# codec.net
KiCad netlist of a schematic drawn in Altium Designer
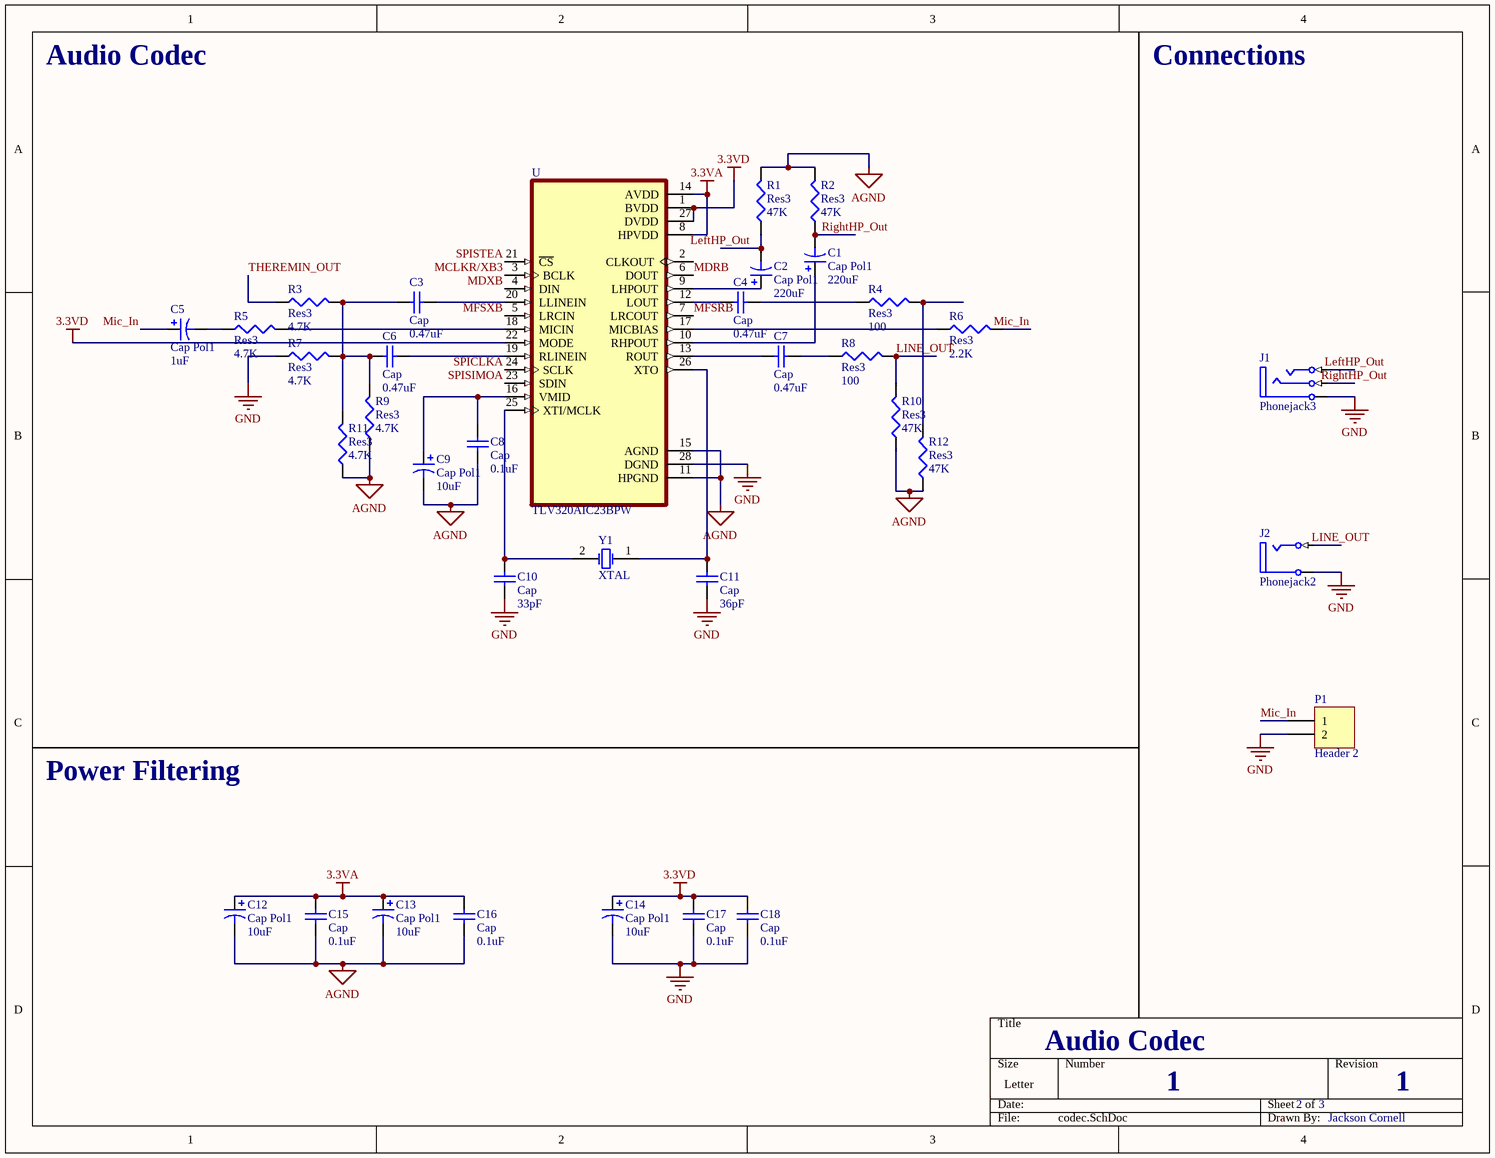
[diagram p0: codec.SchDoc]

(export (version "E")
  (design (tool "Eeschema 10.0.6"))
  (components
    (comp (ref "C1")
      (value "Cap Pol1")
      (footprint "RB7.6-15")
      (description "Polarized Capacitor (Radial)")
      (fields (field (name "ALTIUM_VALUE") "220uF") (field (name "PUBLISHER") "Altium Limited"))
      (libsource (lib "Miscellaneous Devices") (part "Cap Pol1"))
    )
    (comp (ref "C2")
      (value "Cap Pol1")
      (footprint "RB7.6-15")
      (description "Polarized Capacitor (Radial)")
      (fields (field (name "ALTIUM_VALUE") "220uF") (field (name "PUBLISHER") "Altium Limited"))
      (libsource (lib "Miscellaneous Devices") (part "Cap Pol1"))
    )
    (comp (ref "C3")
      (value "Cap")
      (footprint "RAD-0.3")
      (description "Capacitor")
      (fields (field (name "ALTIUM_VALUE") "0.47uF") (field (name "PUBLISHER") "Altium Limited"))
      (libsource (lib "Miscellaneous Devices") (part "Cap"))
    )
    (comp (ref "C4")
      (value "Cap")
      (footprint "RAD-0.3")
      (description "Capacitor")
      (fields (field (name "ALTIUM_VALUE") "0.47uF") (field (name "PUBLISHER") "Altium Limited"))
      (libsource (lib "Miscellaneous Devices") (part "Cap"))
    )
    (comp (ref "C5")
      (value "Cap Pol1")
      (footprint "RB7.6-15")
      (description "Polarized Capacitor (Radial)")
      (fields (field (name "ALTIUM_VALUE") "1uF") (field (name "PUBLISHER") "Altium Limited"))
      (libsource (lib "Miscellaneous Devices") (part "Cap Pol1"))
    )
    (comp (ref "C6")
      (value "Cap")
      (footprint "RAD-0.3")
      (description "Capacitor")
      (fields (field (name "ALTIUM_VALUE") "0.47uF") (field (name "PUBLISHER") "Altium Limited"))
      (libsource (lib "Miscellaneous Devices") (part "Cap"))
    )
    (comp (ref "C7")
      (value "Cap")
      (footprint "RAD-0.3")
      (description "Capacitor")
      (fields (field (name "ALTIUM_VALUE") "0.47uF") (field (name "PUBLISHER") "Altium Limited"))
      (libsource (lib "Miscellaneous Devices") (part "Cap"))
    )
    (comp (ref "C8")
      (value "Cap")
      (footprint "RAD-0.3")
      (description "Capacitor")
      (fields (field (name "ALTIUM_VALUE") "0.1uF") (field (name "PUBLISHER") "Altium Limited"))
      (libsource (lib "Miscellaneous Devices") (part "Cap"))
    )
    (comp (ref "C9")
      (value "Cap Pol1")
      (footprint "RB7.6-15")
      (description "Polarized Capacitor (Radial)")
      (fields (field (name "ALTIUM_VALUE") "10uF") (field (name "PUBLISHER") "Altium Limited"))
      (libsource (lib "Miscellaneous Devices") (part "Cap Pol1"))
    )
    (comp (ref "C10")
      (value "Cap")
      (footprint "RAD-0.3")
      (description "Capacitor")
      (fields (field (name "ALTIUM_VALUE") "33pF") (field (name "PUBLISHER") "Altium Limited"))
      (libsource (lib "Miscellaneous Devices") (part "Cap"))
    )
    (comp (ref "C11")
      (value "Cap")
      (footprint "RAD-0.3")
      (description "Capacitor")
      (fields (field (name "ALTIUM_VALUE") "36pF") (field (name "PUBLISHER") "Altium Limited"))
      (libsource (lib "Miscellaneous Devices") (part "Cap"))
    )
    (comp (ref "C12")
      (value "Cap Pol1")
      (footprint "RB7.6-15")
      (description "Polarized Capacitor (Radial)")
      (fields (field (name "ALTIUM_VALUE") "10uF") (field (name "PUBLISHER") "Altium Limited"))
      (libsource (lib "Miscellaneous Devices") (part "Cap Pol1"))
    )
    (comp (ref "C13")
      (value "Cap Pol1")
      (footprint "RB7.6-15")
      (description "Polarized Capacitor (Radial)")
      (fields (field (name "ALTIUM_VALUE") "10uF") (field (name "PUBLISHER") "Altium Limited"))
      (libsource (lib "Miscellaneous Devices") (part "Cap Pol1"))
    )
    (comp (ref "C14")
      (value "Cap Pol1")
      (footprint "RB7.6-15")
      (description "Polarized Capacitor (Radial)")
      (fields (field (name "ALTIUM_VALUE") "10uF") (field (name "PUBLISHER") "Altium Limited"))
      (libsource (lib "Miscellaneous Devices") (part "Cap Pol1"))
    )
    (comp (ref "C15")
      (value "Cap")
      (footprint "RAD-0.3")
      (description "Capacitor")
      (fields (field (name "ALTIUM_VALUE") "0.1uF") (field (name "PUBLISHER") "Altium Limited"))
      (libsource (lib "Miscellaneous Devices") (part "Cap"))
    )
    (comp (ref "C16")
      (value "Cap")
      (footprint "RAD-0.3")
      (description "Capacitor")
      (fields (field (name "ALTIUM_VALUE") "0.1uF") (field (name "PUBLISHER") "Altium Limited"))
      (libsource (lib "Miscellaneous Devices") (part "Cap"))
    )
    (comp (ref "C17")
      (value "Cap")
      (footprint "RAD-0.3")
      (description "Capacitor")
      (fields (field (name "ALTIUM_VALUE") "0.1uF") (field (name "PUBLISHER") "Altium Limited"))
      (libsource (lib "Miscellaneous Devices") (part "Cap"))
    )
    (comp (ref "C18")
      (value "Cap")
      (footprint "RAD-0.3")
      (description "Capacitor")
      (fields (field (name "ALTIUM_VALUE") "0.1uF") (field (name "PUBLISHER") "Altium Limited"))
      (libsource (lib "Miscellaneous Devices") (part "Cap"))
    )
    (comp (ref "J1")
      (value "Phonejack3")
      (footprint "JACK/6-V3")
      (description "Jack Socket, 1/4\" [6.5mm], Thru-Hole, Vertical, 3-Conductor Open Circuit (Non-Normalling)")
      (fields (field (name "PUBLISHER") "Altium Limited"))
      (libsource (lib "Miscellaneous Connectors") (part "Phonejack3"))
    )
    (comp (ref "J2")
      (value "Phonejack2")
      (footprint "JACK/6-V2")
      (description "Jack Socket, 1/4\" [6.5mm], Thru-Hole, Vertical, 2-Conductor Open Circuit")
      (fields (field (name "PUBLISHER") "Altium Limited"))
      (libsource (lib "Miscellaneous Connectors") (part "Phonejack2"))
    )
    (comp (ref "P1")
      (value "Header 2")
      (footprint "HDR1X2")
      (description "Header, 2-Pin")
      (fields (field (name "PUBLISHER") "Altium Limited"))
      (libsource (lib "Miscellaneous Connectors") (part "Header 2"))
    )
    (comp (ref "R1")
      (value "Res3")
      (footprint "J1-0603")
      (description "Resistor")
      (fields (field (name "ALTIUM_VALUE") "47K") (field (name "PUBLISHER") "Altium Limited"))
      (libsource (lib "Miscellaneous Devices") (part "Res3"))
    )
    (comp (ref "R2")
      (value "Res3")
      (footprint "J1-0603")
      (description "Resistor")
      (fields (field (name "ALTIUM_VALUE") "47K") (field (name "PUBLISHER") "Altium Limited"))
      (libsource (lib "Miscellaneous Devices") (part "Res3"))
    )
    (comp (ref "R3")
      (value "Res3")
      (footprint "J1-0603")
      (description "Resistor")
      (fields (field (name "ALTIUM_VALUE") "4.7K") (field (name "PUBLISHER") "Altium Limited"))
      (libsource (lib "Miscellaneous Devices") (part "Res3"))
    )
    (comp (ref "R4")
      (value "Res3")
      (footprint "J1-0603")
      (description "Resistor")
      (fields (field (name "ALTIUM_VALUE") "100") (field (name "PUBLISHER") "Altium Limited"))
      (libsource (lib "Miscellaneous Devices") (part "Res3"))
    )
    (comp (ref "R5")
      (value "Res3")
      (footprint "J1-0603")
      (description "Resistor")
      (fields (field (name "ALTIUM_VALUE") "4.7K") (field (name "PUBLISHER") "Altium Limited"))
      (libsource (lib "Miscellaneous Devices") (part "Res3"))
    )
    (comp (ref "R6")
      (value "Res3")
      (footprint "J1-0603")
      (description "Resistor")
      (fields (field (name "ALTIUM_VALUE") "2.2K") (field (name "PUBLISHER") "Altium Limited"))
      (libsource (lib "Miscellaneous Devices") (part "Res3"))
    )
    (comp (ref "R7")
      (value "Res3")
      (footprint "J1-0603")
      (description "Resistor")
      (fields (field (name "ALTIUM_VALUE") "4.7K") (field (name "PUBLISHER") "Altium Limited"))
      (libsource (lib "Miscellaneous Devices") (part "Res3"))
    )
    (comp (ref "R8")
      (value "Res3")
      (footprint "J1-0603")
      (description "Resistor")
      (fields (field (name "ALTIUM_VALUE") "100") (field (name "PUBLISHER") "Altium Limited"))
      (libsource (lib "Miscellaneous Devices") (part "Res3"))
    )
    (comp (ref "R9")
      (value "Res3")
      (footprint "J1-0603")
      (description "Resistor")
      (fields (field (name "ALTIUM_VALUE") "4.7K") (field (name "PUBLISHER") "Altium Limited"))
      (libsource (lib "Miscellaneous Devices") (part "Res3"))
    )
    (comp (ref "R10")
      (value "Res3")
      (footprint "J1-0603")
      (description "Resistor")
      (fields (field (name "ALTIUM_VALUE") "47K") (field (name "PUBLISHER") "Altium Limited"))
      (libsource (lib "Miscellaneous Devices") (part "Res3"))
    )
    (comp (ref "R11")
      (value "Res3")
      (footprint "J1-0603")
      (description "Resistor")
      (fields (field (name "ALTIUM_VALUE") "4.7K") (field (name "PUBLISHER") "Altium Limited"))
      (libsource (lib "Miscellaneous Devices") (part "Res3"))
    )
    (comp (ref "R12")
      (value "Res3")
      (footprint "J1-0603")
      (description "Resistor")
      (fields (field (name "ALTIUM_VALUE") "47K") (field (name "PUBLISHER") "Altium Limited"))
      (libsource (lib "Miscellaneous Devices") (part "Res3"))
    )
    (comp (ref "U")
      (value "TLV320AIC23BPW")
      (footprint "SOP65P640X120-28N")
      (description "Low-Power Stereo CODEC with HP Amplifier 28-TSSOP -10 to 70")
      (fields (field (name "MF") "Texas Instruments"))
      (libsource (lib "TLV320AIC23BPW") (part "TLV320AIC23BPW"))
    )
    (comp (ref "Y1")
      (value "XTAL")
      (footprint "R38")
      (description "Crystal Oscillator")
      (fields (field (name "PUBLISHER") "Altium Limited"))
      (libsource (lib "Miscellaneous Devices") (part "XTAL"))
    )
  )
  (nets
    (net (code "1") (name "/LINE_OUT") (class "Default")
      (node (ref "J2") (pin "1") (pinfunction "T_1") (pintype "input"))
      (node (ref "R10") (pin "2") (pinfunction "2_2") (pintype "passive"))
      (node (ref "R8") (pin "2") (pinfunction "2_2") (pintype "passive"))
    )
    (net (code "2") (name "/LeftHP_Out") (class "Default")
      (node (ref "C2") (pin "2") (pinfunction "2_2") (pintype "passive"))
      (node (ref "J1") (pin "1") (pinfunction "T_1") (pintype "input"))
      (node (ref "R1") (pin "1") (pinfunction "1_1") (pintype "passive"))
    )
    (net (code "3") (name "/MCLKR{slash}XB3") (class "Default")
      (node (ref "U") (pin "3") (pinfunction "BCLK_3") (pintype "input"))
    )
    (net (code "4") (name "/MDRB") (class "Default")
      (node (ref "U") (pin "6") (pinfunction "DOUT_6") (pintype "output"))
    )
    (net (code "5") (name "/MDXB") (class "Default")
      (node (ref "U") (pin "4") (pinfunction "DIN_4") (pintype "input"))
    )
    (net (code "6") (name "/MFSRB") (class "Default")
      (node (ref "U") (pin "7") (pinfunction "LRCOUT_7") (pintype "output"))
    )
    (net (code "7") (name "/MFSXB") (class "Default")
      (node (ref "U") (pin "5") (pinfunction "LRCIN_5") (pintype "input"))
    )
    (net (code "8") (name "/Mic_In") (class "Default")
      (node (ref "C5") (pin "1") (pinfunction "1_1") (pintype "passive"))
      (node (ref "P1") (pin "1") (pinfunction "1_1") (pintype "passive"))
      (node (ref "R6") (pin "2") (pinfunction "2_2") (pintype "passive"))
    )
    (net (code "9") (name "/RightHP_Out") (class "Default")
      (node (ref "C1") (pin "2") (pinfunction "2_2") (pintype "passive"))
      (node (ref "J1") (pin "3") (pinfunction "R_3") (pintype "input"))
      (node (ref "R2") (pin "1") (pinfunction "1_1") (pintype "passive"))
    )
    (net (code "10") (name "/SPICLKA") (class "Default")
      (node (ref "U") (pin "24") (pinfunction "SCLK_24") (pintype "input"))
    )
    (net (code "11") (name "/SPISIMOA") (class "Default")
      (node (ref "U") (pin "23") (pinfunction "SDIN_23") (pintype "input"))
    )
    (net (code "12") (name "/SPISTEA") (class "Default")
      (node (ref "U") (pin "21") (pinfunction "~{CS}_21") (pintype "input"))
    )
    (net (code "13") (name "/THEREMIN_OUT") (class "Default")
      (node (ref "R3") (pin "1") (pinfunction "1_1") (pintype "passive"))
    )
    (net (code "14") (name "3.3VA") (class "Default")
      (node (ref "C12") (pin "1") (pinfunction "1_1") (pintype "passive"))
      (node (ref "C13") (pin "1") (pinfunction "1_1") (pintype "passive"))
      (node (ref "C15") (pin "1") (pinfunction "1_1") (pintype "passive"))
      (node (ref "C16") (pin "1") (pinfunction "1_1") (pintype "passive"))
      (node (ref "U") (pin "14") (pinfunction "AVDD_14") (pintype "power_in"))
      (node (ref "U") (pin "8") (pinfunction "HPVDD_8") (pintype "power_in"))
    )
    (net (code "15") (name "3.3VD") (class "Default")
      (node (ref "C14") (pin "1") (pinfunction "1_1") (pintype "passive"))
      (node (ref "C17") (pin "2") (pinfunction "2_2") (pintype "passive"))
      (node (ref "C18") (pin "2") (pinfunction "2_2") (pintype "passive"))
      (node (ref "U") (pin "1") (pinfunction "BVDD_1") (pintype "power_in"))
      (node (ref "U") (pin "22") (pinfunction "MODE_22") (pintype "input"))
      (node (ref "U") (pin "27") (pinfunction "DVDD_27") (pintype "power_in"))
    )
    (net (code "16") (name "AGND") (class "Default")
      (node (ref "C12") (pin "2") (pinfunction "2_2") (pintype "passive"))
      (node (ref "C13") (pin "2") (pinfunction "2_2") (pintype "passive"))
      (node (ref "C15") (pin "2") (pinfunction "2_2") (pintype "passive"))
      (node (ref "C16") (pin "2") (pinfunction "2_2") (pintype "passive"))
      (node (ref "C8") (pin "1") (pinfunction "1_1") (pintype "passive"))
      (node (ref "C9") (pin "2") (pinfunction "2_2") (pintype "passive"))
      (node (ref "R1") (pin "2") (pinfunction "2_2") (pintype "passive"))
      (node (ref "R10") (pin "1") (pinfunction "1_1") (pintype "passive"))
      (node (ref "R11") (pin "1") (pinfunction "1_1") (pintype "passive"))
      (node (ref "R12") (pin "1") (pinfunction "1_1") (pintype "passive"))
      (node (ref "R2") (pin "2") (pinfunction "2_2") (pintype "passive"))
      (node (ref "R9") (pin "1") (pinfunction "1_1") (pintype "passive"))
      (node (ref "U") (pin "11") (pinfunction "HPGND_11") (pintype "power_in"))
      (node (ref "U") (pin "15") (pinfunction "AGND_15") (pintype "power_in"))
    )
    (net (code "17") (name "GND") (class "Default")
      (node (ref "C10") (pin "2") (pinfunction "2_2") (pintype "passive"))
      (node (ref "C11") (pin "2") (pinfunction "2_2") (pintype "passive"))
      (node (ref "C14") (pin "2") (pinfunction "2_2") (pintype "passive"))
      (node (ref "C17") (pin "1") (pinfunction "1_1") (pintype "passive"))
      (node (ref "C18") (pin "1") (pinfunction "1_1") (pintype "passive"))
      (node (ref "J1") (pin "5") (pinfunction "S_5") (pintype "power_in"))
      (node (ref "J2") (pin "5") (pinfunction "S_5") (pintype "power_in"))
      (node (ref "P1") (pin "2") (pinfunction "2_2") (pintype "passive"))
      (node (ref "R7") (pin "1") (pinfunction "1_1") (pintype "passive"))
      (node (ref "U") (pin "28") (pinfunction "DGND_28") (pintype "power_in"))
    )
    (net (code "18") (name "Net-(C3-Pad1)") (class "Default")
      (node (ref "C3") (pin "1") (pinfunction "1_1") (pintype "passive"))
      (node (ref "C6") (pin "1") (pinfunction "1_1") (pintype "passive"))
      (node (ref "R11") (pin "2") (pinfunction "2_2") (pintype "passive"))
      (node (ref "R3") (pin "2") (pinfunction "2_2") (pintype "passive"))
      (node (ref "R7") (pin "2") (pinfunction "2_2") (pintype "passive"))
      (node (ref "R9") (pin "2") (pinfunction "2_2") (pintype "passive"))
    )
    (net (code "19") (name "Net-(C4-Pad2)") (class "Default")
      (node (ref "C4") (pin "2") (pinfunction "2_2") (pintype "passive"))
      (node (ref "R4") (pin "1") (pinfunction "1_1") (pintype "passive"))
    )
    (net (code "20") (name "Net-(C5-Pad2)") (class "Default")
      (node (ref "C5") (pin "2") (pinfunction "2_2") (pintype "passive"))
      (node (ref "R5") (pin "1") (pinfunction "1_1") (pintype "passive"))
    )
    (net (code "21") (name "Net-(C7-Pad2)") (class "Default")
      (node (ref "C7") (pin "2") (pinfunction "2_2") (pintype "passive"))
      (node (ref "R8") (pin "1") (pinfunction "1_1") (pintype "passive"))
    )
    (net (code "22") (name "Net-(R12-Pad2)") (class "Default")
      (node (ref "R12") (pin "2") (pinfunction "2_2") (pintype "passive"))
      (node (ref "R4") (pin "2") (pinfunction "2_2") (pintype "passive"))
    )
    (net (code "23") (name "Net-(U-LHPOUT)") (class "Default")
      (node (ref "C2") (pin "1") (pinfunction "1_1") (pintype "passive"))
      (node (ref "U") (pin "9") (pinfunction "LHPOUT_9") (pintype "output"))
    )
    (net (code "24") (name "Net-(U-LLINEIN)") (class "Default")
      (node (ref "C3") (pin "2") (pinfunction "2_2") (pintype "passive"))
      (node (ref "U") (pin "20") (pinfunction "LLINEIN_20") (pintype "input"))
    )
    (net (code "25") (name "Net-(U-LOUT)") (class "Default")
      (node (ref "C4") (pin "1") (pinfunction "1_1") (pintype "passive"))
      (node (ref "U") (pin "12") (pinfunction "LOUT_12") (pintype "output"))
    )
    (net (code "26") (name "Net-(U-MICBIAS)") (class "Default")
      (node (ref "R6") (pin "1") (pinfunction "1_1") (pintype "passive"))
      (node (ref "U") (pin "17") (pinfunction "MICBIAS_17") (pintype "output"))
    )
    (net (code "27") (name "Net-(U-MICIN)") (class "Default")
      (node (ref "R5") (pin "2") (pinfunction "2_2") (pintype "passive"))
      (node (ref "U") (pin "18") (pinfunction "MICIN_18") (pintype "input"))
    )
    (net (code "28") (name "Net-(U-RHPOUT)") (class "Default")
      (node (ref "C1") (pin "1") (pinfunction "1_1") (pintype "passive"))
      (node (ref "U") (pin "10") (pinfunction "RHPOUT_10") (pintype "output"))
    )
    (net (code "29") (name "Net-(U-RLINEIN)") (class "Default")
      (node (ref "C6") (pin "2") (pinfunction "2_2") (pintype "passive"))
      (node (ref "U") (pin "19") (pinfunction "RLINEIN_19") (pintype "input"))
    )
    (net (code "30") (name "Net-(U-ROUT)") (class "Default")
      (node (ref "C7") (pin "1") (pinfunction "1_1") (pintype "passive"))
      (node (ref "U") (pin "13") (pinfunction "ROUT_13") (pintype "output"))
    )
    (net (code "31") (name "Net-(U-VMID)") (class "Default")
      (node (ref "C8") (pin "2") (pinfunction "2_2") (pintype "passive"))
      (node (ref "C9") (pin "1") (pinfunction "1_1") (pintype "passive"))
      (node (ref "U") (pin "16") (pinfunction "VMID_16") (pintype "input"))
    )
    (net (code "32") (name "Net-(U-XTI{slash}MCLK)") (class "Default")
      (node (ref "C10") (pin "1") (pinfunction "1_1") (pintype "passive"))
      (node (ref "U") (pin "25") (pinfunction "XTI/MCLK_25") (pintype "input"))
      (node (ref "Y1") (pin "2") (pinfunction "OSC2_2") (pintype "passive"))
    )
    (net (code "33") (name "Net-(U-XTO)") (class "Default")
      (node (ref "C11") (pin "1") (pinfunction "1_1") (pintype "passive"))
      (node (ref "U") (pin "26") (pinfunction "XTO_26") (pintype "output"))
      (node (ref "Y1") (pin "1") (pinfunction "OSC1_1") (pintype "passive"))
    )
    (net (code "34") (name "unconnected-(U-CLKOUT-Pad2)") (class "Default")
      (node (ref "U") (pin "2") (pinfunction "CLKOUT_2") (pintype "output"))
    )
  )
)
